# Board_v2.net
KiCad netlist of a schematic drawn in EAGLE
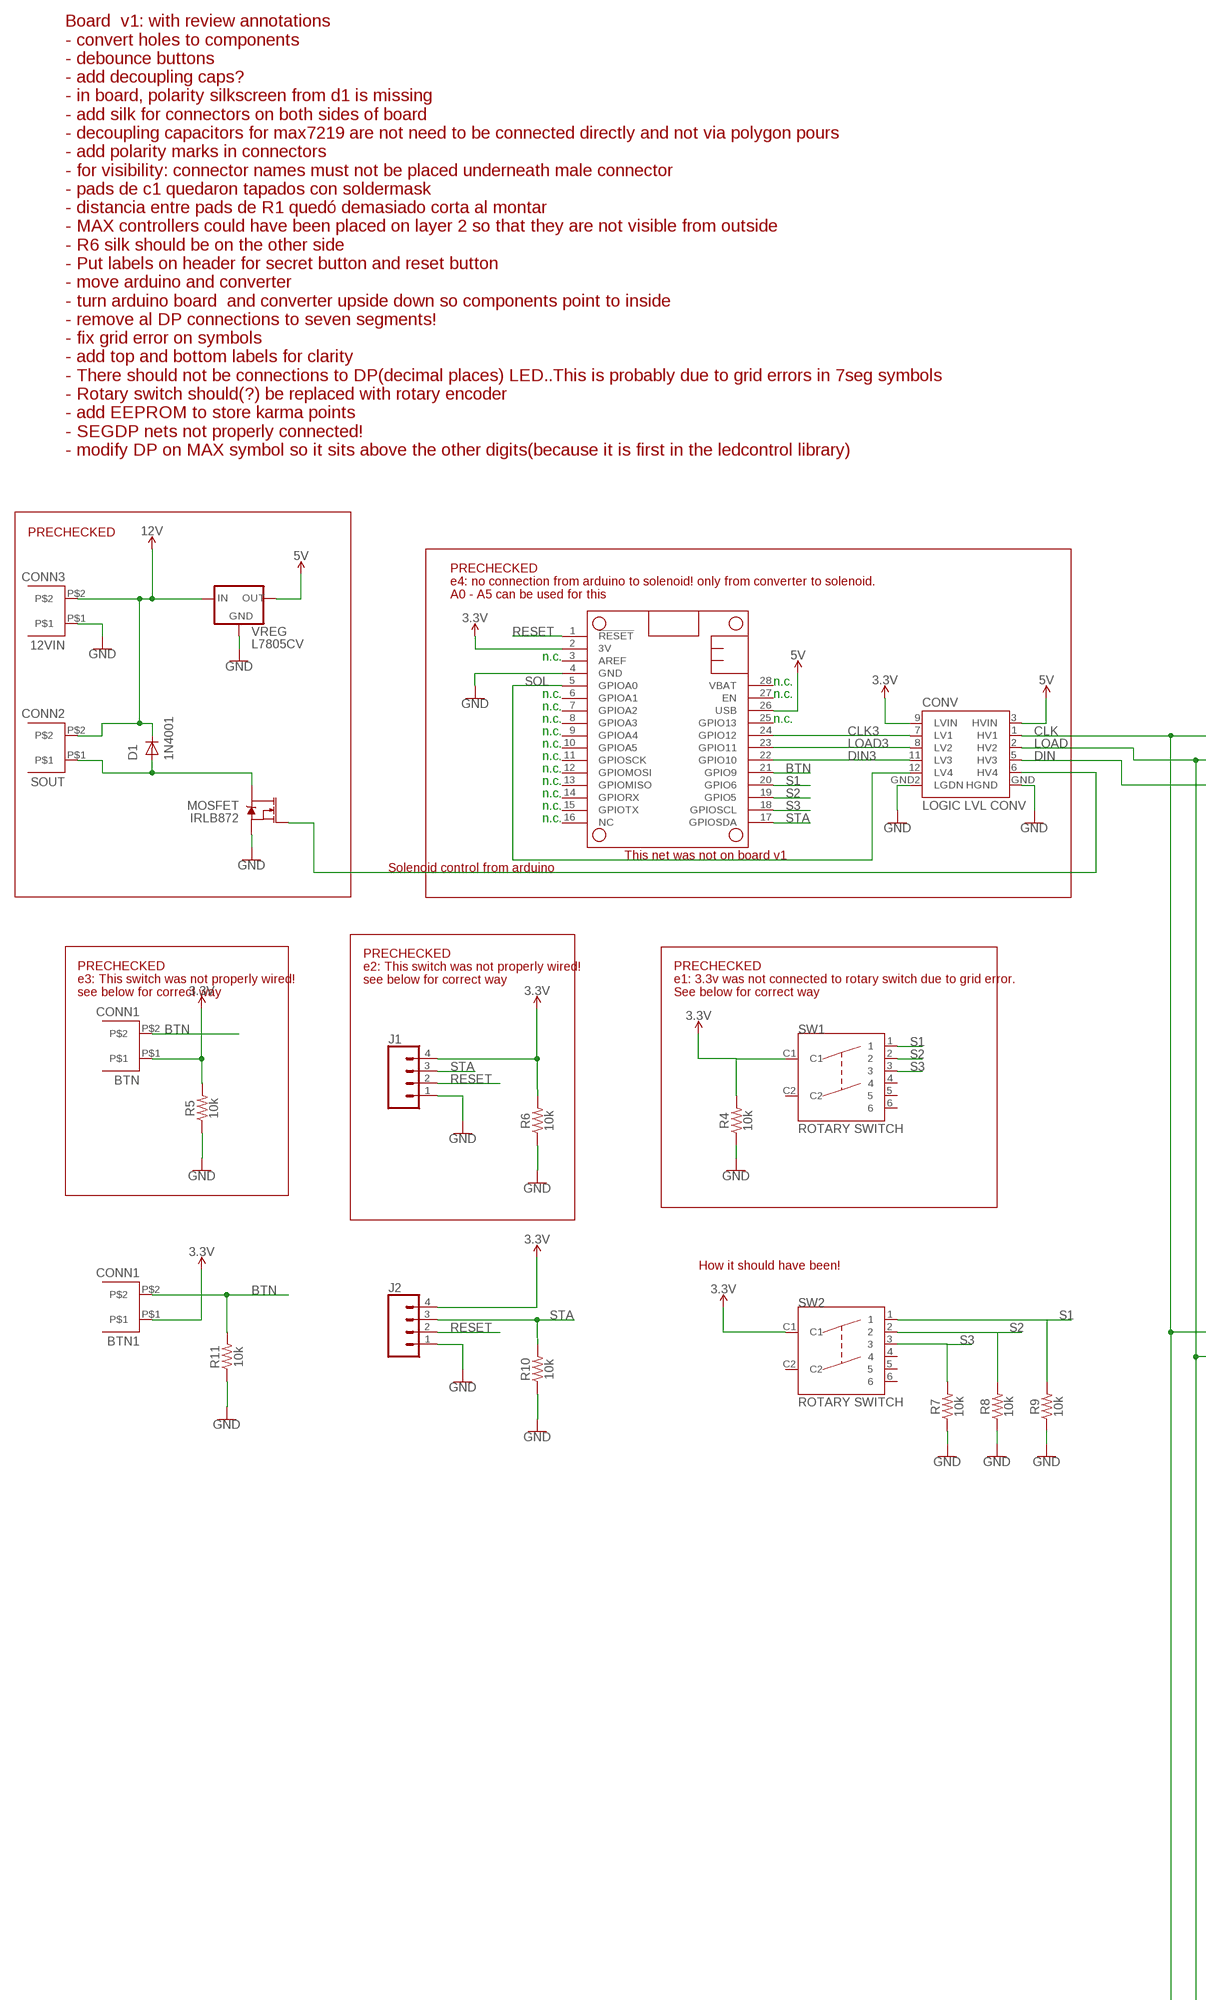
[diagram p0: schematic, sheet 1, part 1 of 3]
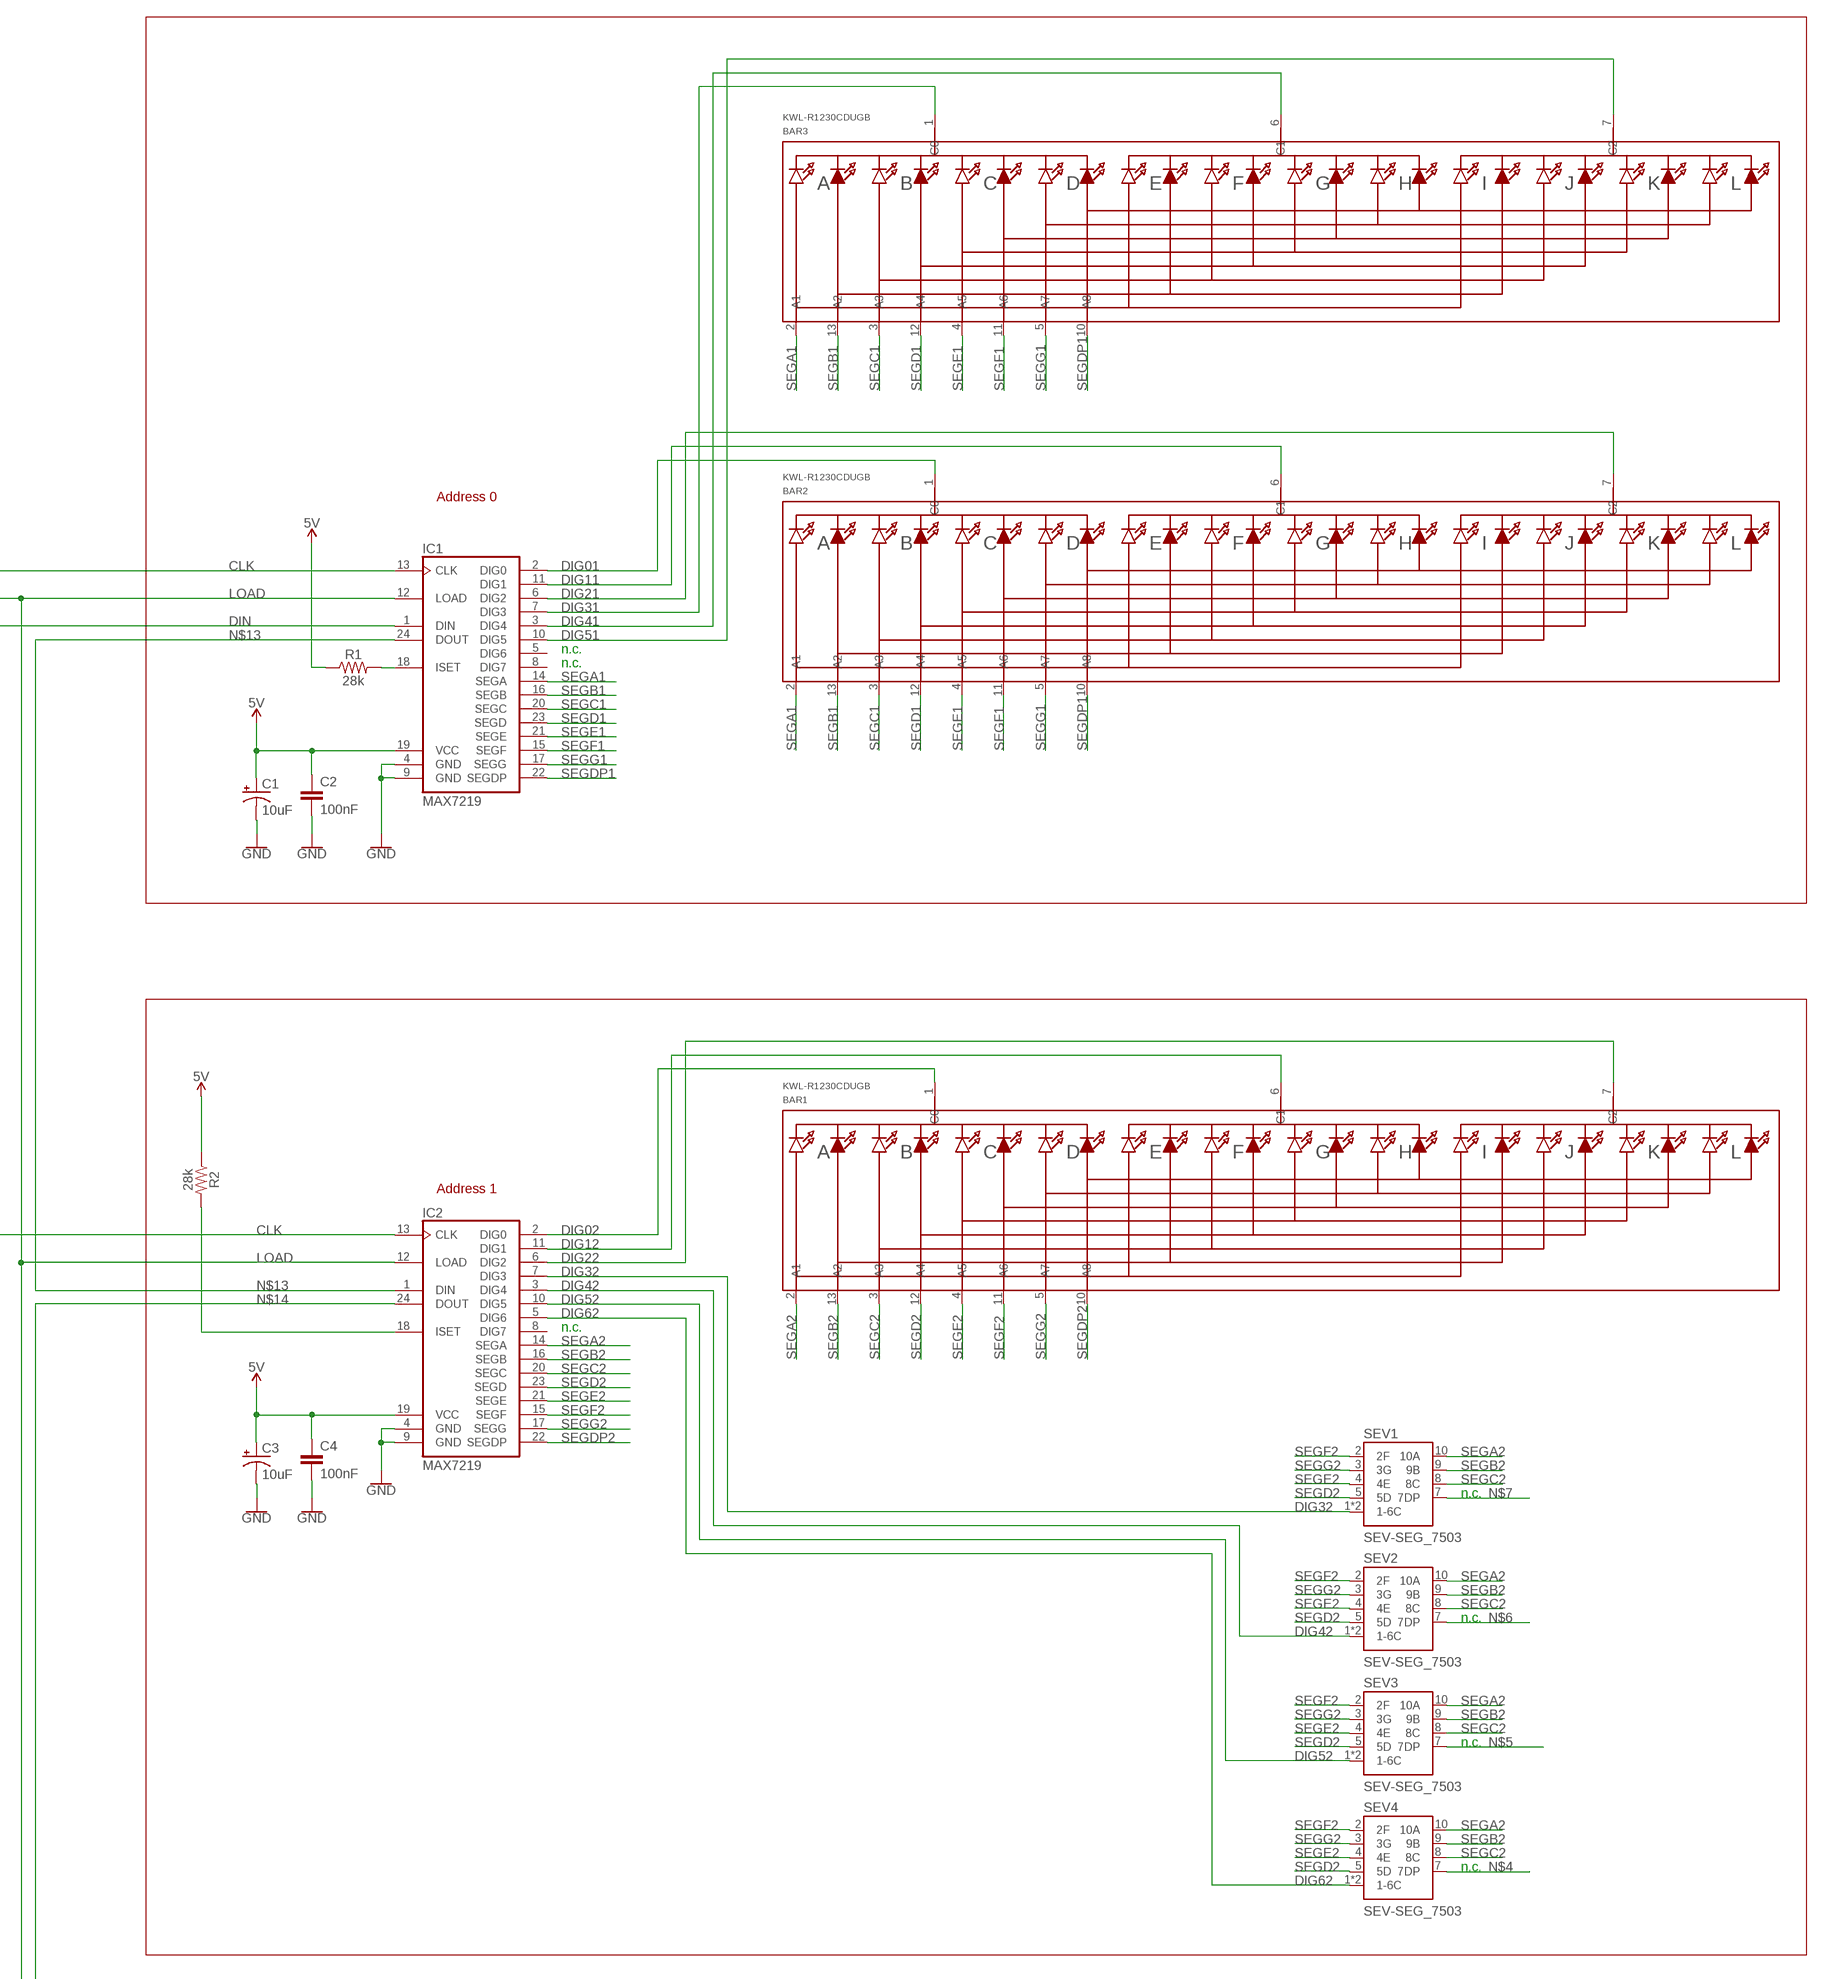
[diagram p1: schematic, sheet 1, part 2 of 3]
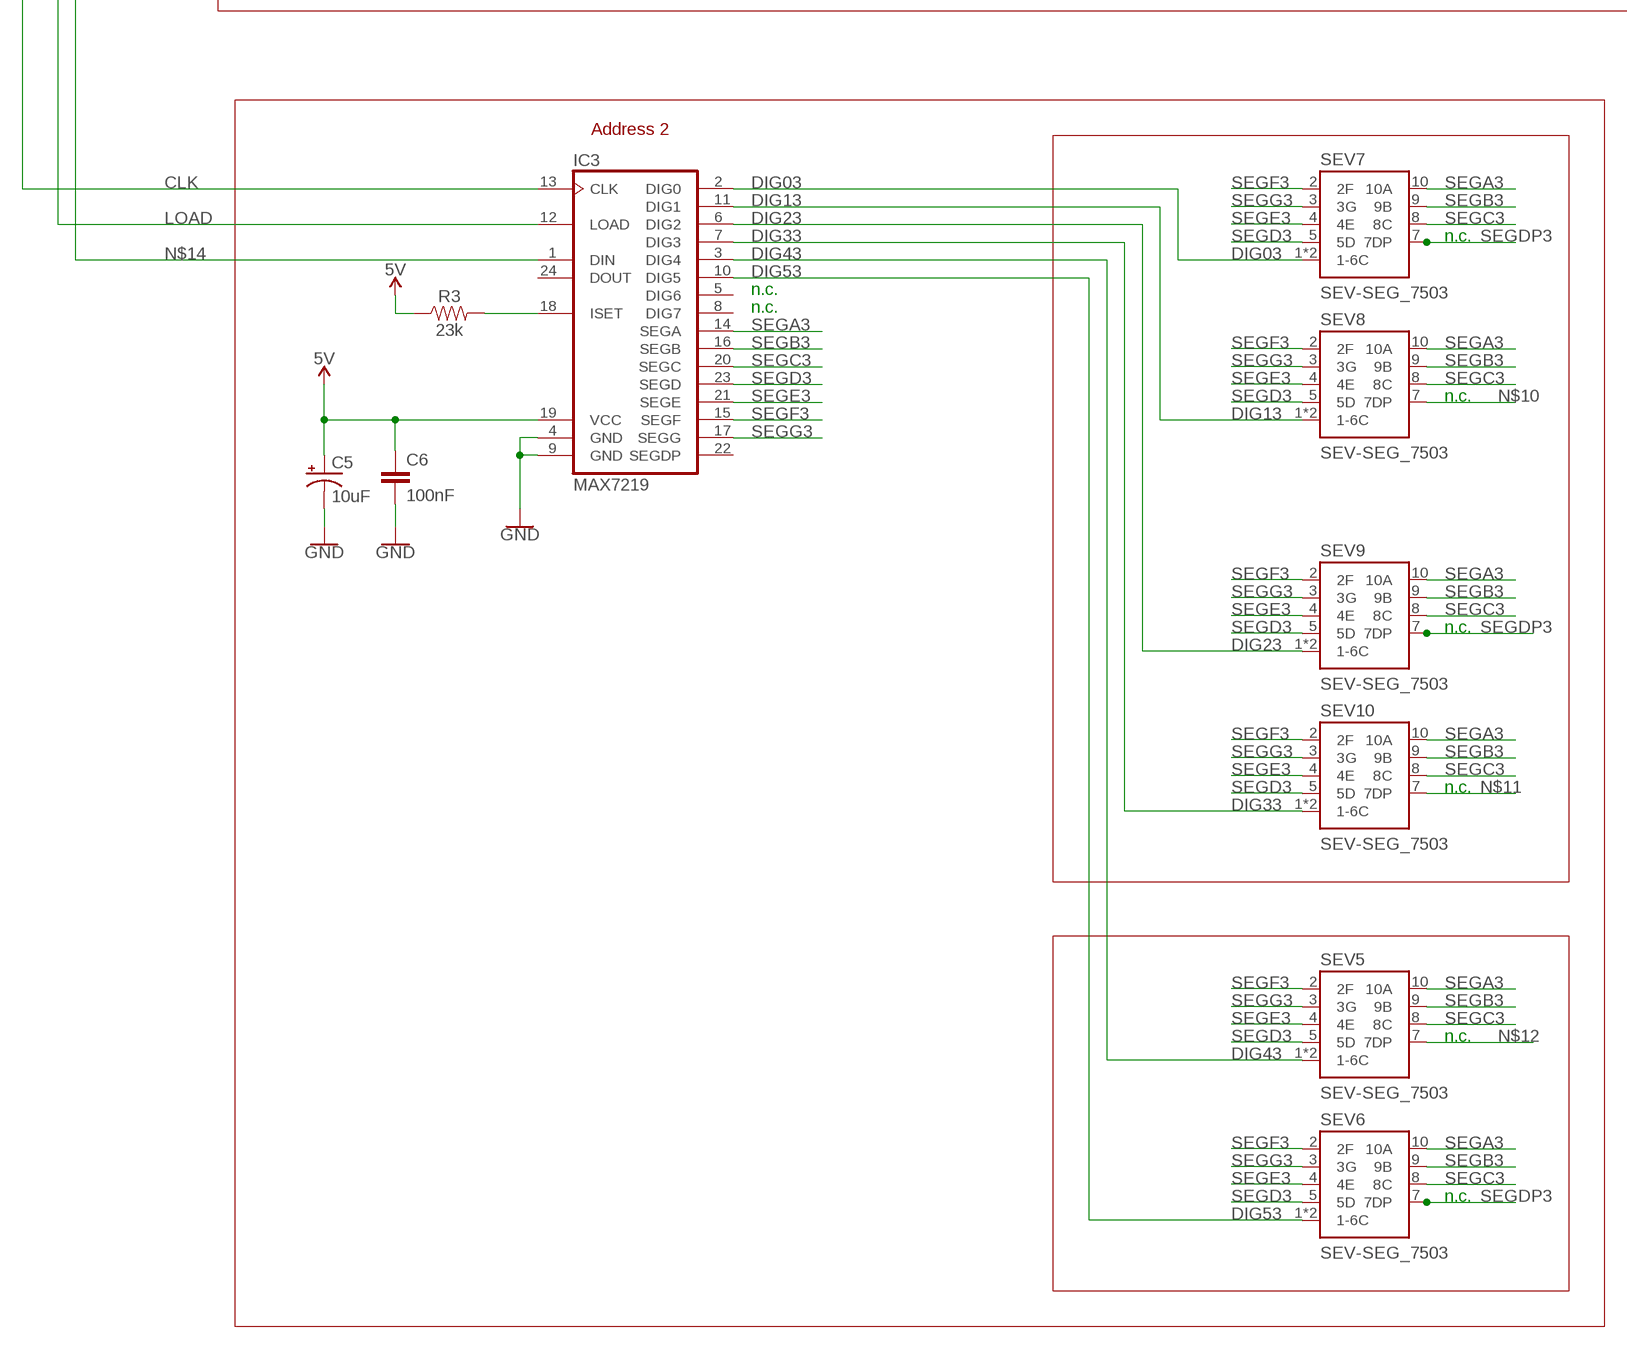
[diagram p2: schematic, sheet 1, part 3 of 3]

(export (version "E")
  (design (tool "Eeschema 10.0.6"))
  (components
    (comp (ref "12VIN")
      (value "CONN3")
      (footprint "eagle-import:MICRO-FIT_43560_3MM")
      (libsource (lib "eagle-import") (part "MICRO-FIT_3.0_43650"))
    )
    (comp (ref "BAR1")
      (value "KWL-R1230CDUGB")
      (footprint "eagle-import:SEGMENT_BICOL_BL-AR12Z3010")
      (libsource (lib "eagle-import") (part "KWL-R1230CDUGB"))
    )
    (comp (ref "BAR2")
      (value "KWL-R1230CDUGB")
      (footprint "eagle-import:SEGMENT_BICOL_BL-AR12Z3010")
      (libsource (lib "eagle-import") (part "KWL-R1230CDUGB"))
    )
    (comp (ref "BAR3")
      (value "KWL-R1230CDUGB")
      (footprint "eagle-import:SEGMENT_BICOL_BL-AR12Z3010")
      (libsource (lib "eagle-import") (part "KWL-R1230CDUGB"))
    )
    (comp (ref "BTN")
      (value "CONN1")
      (footprint "eagle-import:MICRO-FIT_43560_3MM")
      (libsource (lib "eagle-import") (part "MICRO-FIT_3.0_43650"))
    )
    (comp (ref "BTN1")
      (value "CONN1")
      (footprint "eagle-import:MICRO-FIT_43560_3MM")
      (libsource (lib "eagle-import") (part "MICRO-FIT_3.0_43650"))
    )
    (comp (ref "C1")
      (value "10uF")
      (footprint "eagle-import:CPOL-RADIAL-2.5MM-5MM-KIT")
      (libsource (lib "eagle-import") (part "CAP_POL"))
    )
    (comp (ref "C2")
      (value "100nF")
      (footprint "eagle-import:CAP-PTH-5MM")
      (libsource (lib "eagle-import") (part "CAP_CERAMIC"))
    )
    (comp (ref "C3")
      (value "10uF")
      (footprint "eagle-import:CPOL-RADIAL-2.5MM-5MM-KIT")
      (libsource (lib "eagle-import") (part "CAP_POL"))
    )
    (comp (ref "C4")
      (value "100nF")
      (footprint "eagle-import:CAP-PTH-5MM")
      (libsource (lib "eagle-import") (part "CAP_CERAMIC"))
    )
    (comp (ref "C5")
      (value "10uF")
      (footprint "eagle-import:CPOL-RADIAL-2.5MM-5MM-KIT")
      (libsource (lib "eagle-import") (part "CAP_POL"))
    )
    (comp (ref "C6")
      (value "100nF")
      (footprint "eagle-import:CAP-PTH-5MM")
      (libsource (lib "eagle-import") (part "CAP_CERAMIC"))
    )
    (comp (ref "CONV")
      (value "LOGIC LVL CONV")
      (footprint "eagle-import:3-5V_LOGIC_LVL_CONV")
      (libsource (lib "eagle-import") (part "3-5V_LOGIC_LVL_CONV"))
    )
    (comp (ref "D1")
      (value "1N4001")
      (footprint "eagle-import:CASE59−10-AXIAL")
      (libsource (lib "eagle-import") (part "1N4001"))
    )
    (comp (ref "FEATHERM0")
      (value "FEATHERWING_NODIM")
      (footprint "eagle-import:FEATHER")
      (libsource (lib "eagle-import") (part "FEATHERWING_NODIM"))
    )
    (comp (ref "IC1")
      (value "MAX7219")
      (footprint "eagle-import:DIL24-3")
      (fields (field (name "MF") "MAXIM") (field (name "MPN") "MAX7219CNG"))
      (libsource (lib "eagle-import") (part "MAX7219CNG"))
    )
    (comp (ref "IC2")
      (value "MAX7219")
      (footprint "eagle-import:DIL24-3")
      (fields (field (name "MF") "MAXIM") (field (name "MPN") "MAX7219CNG"))
      (libsource (lib "eagle-import") (part "MAX7219CNG"))
    )
    (comp (ref "IC3")
      (value "MAX7219")
      (footprint "eagle-import:DIL24-3")
      (fields (field (name "MF") "MAXIM") (field (name "MPN") "MAX7219CNG"))
      (libsource (lib "eagle-import") (part "MAX7219CNG"))
    )
    (comp (ref "J1")
      (value "CONN_041X04_NO_SILK")
      (footprint "eagle-import:1X04_NO_SILK")
      (libsource (lib "eagle-import") (part "CONN_041X04_NO_SILK"))
    )
    (comp (ref "J2")
      (value "CONN_041X04_NO_SILK")
      (footprint "eagle-import:1X04_NO_SILK")
      (libsource (lib "eagle-import") (part "CONN_041X04_NO_SILK"))
    )
    (comp (ref "MOSFET")
      (value "IRLB872")
      (footprint "eagle-import:TO-220-ALT")
      (libsource (lib "eagle-import") (part "IRLB872"))
    )
    (comp (ref "R1")
      (value "28k")
      (footprint "eagle-import:AXIAL-0.3")
      (libsource (lib "eagle-import") (part "RESISTOR"))
    )
    (comp (ref "R2")
      (value "28k")
      (footprint "eagle-import:AXIAL-0.3")
      (libsource (lib "eagle-import") (part "RESISTOR"))
    )
    (comp (ref "R3")
      (value "23k")
      (footprint "eagle-import:AXIAL-0.3")
      (libsource (lib "eagle-import") (part "RESISTOR"))
    )
    (comp (ref "R4")
      (value "10k")
      (footprint "eagle-import:AXIAL-0.3")
      (libsource (lib "eagle-import") (part "RESISTOR"))
    )
    (comp (ref "R5")
      (value "10k")
      (footprint "eagle-import:AXIAL-0.3")
      (libsource (lib "eagle-import") (part "RESISTOR"))
    )
    (comp (ref "R6")
      (value "10k")
      (footprint "eagle-import:AXIAL-0.3")
      (libsource (lib "eagle-import") (part "RESISTOR"))
    )
    (comp (ref "R7")
      (value "10k")
      (footprint "eagle-import:AXIAL-0.3")
      (libsource (lib "eagle-import") (part "RESISTOR"))
    )
    (comp (ref "R8")
      (value "10k")
      (footprint "eagle-import:AXIAL-0.3")
      (libsource (lib "eagle-import") (part "RESISTOR"))
    )
    (comp (ref "R9")
      (value "10k")
      (footprint "eagle-import:AXIAL-0.3")
      (libsource (lib "eagle-import") (part "RESISTOR"))
    )
    (comp (ref "R10")
      (value "10k")
      (footprint "eagle-import:AXIAL-0.3")
      (libsource (lib "eagle-import") (part "RESISTOR"))
    )
    (comp (ref "R11")
      (value "10k")
      (footprint "eagle-import:AXIAL-0.3")
      (libsource (lib "eagle-import") (part "RESISTOR"))
    )
    (comp (ref "SEV1")
      (value "SEV-SEG_7503")
      (footprint "eagle-import:HDSP-7503-C")
      (libsource (lib "eagle-import") (part "SEV-SEG_7503"))
    )
    (comp (ref "SEV2")
      (value "SEV-SEG_7503")
      (footprint "eagle-import:HDSP-7503-C")
      (libsource (lib "eagle-import") (part "SEV-SEG_7503"))
    )
    (comp (ref "SEV3")
      (value "SEV-SEG_7503")
      (footprint "eagle-import:HDSP-7503-C")
      (libsource (lib "eagle-import") (part "SEV-SEG_7503"))
    )
    (comp (ref "SEV4")
      (value "SEV-SEG_7503")
      (footprint "eagle-import:HDSP-7503-C")
      (libsource (lib "eagle-import") (part "SEV-SEG_7503"))
    )
    (comp (ref "SEV5")
      (value "SEV-SEG_7503")
      (footprint "eagle-import:HDSP-7503-C")
      (libsource (lib "eagle-import") (part "SEV-SEG_7503"))
    )
    (comp (ref "SEV6")
      (value "SEV-SEG_7503")
      (footprint "eagle-import:HDSP-7503-C")
      (libsource (lib "eagle-import") (part "SEV-SEG_7503"))
    )
    (comp (ref "SEV7")
      (value "SEV-SEG_7503")
      (footprint "eagle-import:HDSP-7503-C")
      (libsource (lib "eagle-import") (part "SEV-SEG_7503"))
    )
    (comp (ref "SEV8")
      (value "SEV-SEG_7503")
      (footprint "eagle-import:HDSP-7503-C")
      (libsource (lib "eagle-import") (part "SEV-SEG_7503"))
    )
    (comp (ref "SEV9")
      (value "SEV-SEG_7503")
      (footprint "eagle-import:HDSP-7503-C")
      (libsource (lib "eagle-import") (part "SEV-SEG_7503"))
    )
    (comp (ref "SEV10")
      (value "SEV-SEG_7503")
      (footprint "eagle-import:HDSP-7503-C")
      (libsource (lib "eagle-import") (part "SEV-SEG_7503"))
    )
    (comp (ref "SOUT")
      (value "CONN2")
      (footprint "eagle-import:MICRO-FIT_43560_3MM")
      (libsource (lib "eagle-import") (part "MICRO-FIT_3.0_43650"))
    )
    (comp (ref "SW1")
      (value "ROTARY SWITCH")
      (footprint "eagle-import:MRB24B_SP3T")
      (libsource (lib "eagle-import") (part "MRB_ROTARY_SWITCH"))
    )
    (comp (ref "SW2")
      (value "ROTARY SWITCH")
      (footprint "eagle-import:MRB24B_SP3T")
      (libsource (lib "eagle-import") (part "MRB_ROTARY_SWITCH"))
    )
    (comp (ref "VREG")
      (value "L7805CV")
      (footprint "eagle-import:TO-220-ALT")
      (libsource (lib "eagle-import") (part "L7805CV"))
    )
  )
  (nets
    (net (code "1") (name "/BTN") (class "Default")
      (node (ref "BTN") (pin "P$2") (pinfunction "P$2_P$2") (pintype "bidirectional"))
      (node (ref "BTN1") (pin "P$2") (pinfunction "P$2_P$2") (pintype "bidirectional"))
      (node (ref "FEATHERM0") (pin "21") (pinfunction "GPIO9_21") (pintype "bidirectional"))
      (node (ref "R11") (pin "P$2") (pinfunction "2_P$2") (pintype "passive"))
    )
    (net (code "2") (name "/CLK") (class "Default")
      (node (ref "CONV") (pin "1") (pinfunction "HV1_1") (pintype "bidirectional"))
      (node (ref "IC1") (pin "13") (pinfunction "CLK_13") (pintype "input"))
      (node (ref "IC2") (pin "13") (pinfunction "CLK_13") (pintype "input"))
      (node (ref "IC3") (pin "13") (pinfunction "CLK_13") (pintype "input"))
    )
    (net (code "3") (name "/CLK3") (class "Default")
      (node (ref "CONV") (pin "7") (pinfunction "LV1_7") (pintype "bidirectional"))
      (node (ref "FEATHERM0") (pin "24") (pinfunction "GPIO12_24") (pintype "bidirectional"))
    )
    (net (code "4") (name "/DIG01") (class "Default")
      (node (ref "BAR2") (pin "1") (pinfunction "C0_1") (pintype "bidirectional"))
      (node (ref "IC1") (pin "2") (pinfunction "DIG0_2") (pintype "output"))
    )
    (net (code "5") (name "/DIG02") (class "Default")
      (node (ref "BAR1") (pin "1") (pinfunction "C0_1") (pintype "bidirectional"))
      (node (ref "IC2") (pin "2") (pinfunction "DIG0_2") (pintype "output"))
    )
    (net (code "6") (name "/DIG03") (class "Default")
      (node (ref "IC3") (pin "2") (pinfunction "DIG0_2") (pintype "output"))
      (node (ref "SEV7") (pin "1") (pinfunction "1-6C_1") (pintype "bidirectional"))
      (node (ref "SEV7") (pin "6") (pinfunction "1-6C_6") (pintype "bidirectional"))
    )
    (net (code "7") (name "/DIG11") (class "Default")
      (node (ref "BAR2") (pin "6") (pinfunction "C1_6") (pintype "bidirectional"))
      (node (ref "IC1") (pin "11") (pinfunction "DIG1_11") (pintype "output"))
    )
    (net (code "8") (name "/DIG12") (class "Default")
      (node (ref "BAR1") (pin "6") (pinfunction "C1_6") (pintype "bidirectional"))
      (node (ref "IC2") (pin "11") (pinfunction "DIG1_11") (pintype "output"))
    )
    (net (code "9") (name "/DIG13") (class "Default")
      (node (ref "IC3") (pin "11") (pinfunction "DIG1_11") (pintype "output"))
      (node (ref "SEV8") (pin "1") (pinfunction "1-6C_1") (pintype "bidirectional"))
      (node (ref "SEV8") (pin "6") (pinfunction "1-6C_6") (pintype "bidirectional"))
    )
    (net (code "10") (name "/DIG21") (class "Default")
      (node (ref "BAR2") (pin "7") (pinfunction "C2_7") (pintype "bidirectional"))
      (node (ref "IC1") (pin "6") (pinfunction "DIG2_6") (pintype "output"))
    )
    (net (code "11") (name "/DIG22") (class "Default")
      (node (ref "BAR1") (pin "7") (pinfunction "C2_7") (pintype "bidirectional"))
      (node (ref "IC2") (pin "6") (pinfunction "DIG2_6") (pintype "output"))
    )
    (net (code "12") (name "/DIG23") (class "Default")
      (node (ref "IC3") (pin "6") (pinfunction "DIG2_6") (pintype "output"))
      (node (ref "SEV9") (pin "1") (pinfunction "1-6C_1") (pintype "bidirectional"))
      (node (ref "SEV9") (pin "6") (pinfunction "1-6C_6") (pintype "bidirectional"))
    )
    (net (code "13") (name "/DIG31") (class "Default")
      (node (ref "BAR3") (pin "1") (pinfunction "C0_1") (pintype "bidirectional"))
      (node (ref "IC1") (pin "7") (pinfunction "DIG3_7") (pintype "output"))
    )
    (net (code "14") (name "/DIG32") (class "Default")
      (node (ref "IC2") (pin "7") (pinfunction "DIG3_7") (pintype "output"))
      (node (ref "SEV1") (pin "1") (pinfunction "1-6C_1") (pintype "bidirectional"))
      (node (ref "SEV1") (pin "6") (pinfunction "1-6C_6") (pintype "bidirectional"))
    )
    (net (code "15") (name "/DIG33") (class "Default")
      (node (ref "IC3") (pin "7") (pinfunction "DIG3_7") (pintype "output"))
      (node (ref "SEV10") (pin "1") (pinfunction "1-6C_1") (pintype "bidirectional"))
      (node (ref "SEV10") (pin "6") (pinfunction "1-6C_6") (pintype "bidirectional"))
    )
    (net (code "16") (name "/DIG41") (class "Default")
      (node (ref "BAR3") (pin "6") (pinfunction "C1_6") (pintype "bidirectional"))
      (node (ref "IC1") (pin "3") (pinfunction "DIG4_3") (pintype "output"))
    )
    (net (code "17") (name "/DIG42") (class "Default")
      (node (ref "IC2") (pin "3") (pinfunction "DIG4_3") (pintype "output"))
      (node (ref "SEV2") (pin "1") (pinfunction "1-6C_1") (pintype "bidirectional"))
      (node (ref "SEV2") (pin "6") (pinfunction "1-6C_6") (pintype "bidirectional"))
    )
    (net (code "18") (name "/DIG43") (class "Default")
      (node (ref "IC3") (pin "3") (pinfunction "DIG4_3") (pintype "output"))
      (node (ref "SEV5") (pin "1") (pinfunction "1-6C_1") (pintype "bidirectional"))
      (node (ref "SEV5") (pin "6") (pinfunction "1-6C_6") (pintype "bidirectional"))
    )
    (net (code "19") (name "/DIG51") (class "Default")
      (node (ref "BAR3") (pin "7") (pinfunction "C2_7") (pintype "bidirectional"))
      (node (ref "IC1") (pin "10") (pinfunction "DIG5_10") (pintype "output"))
    )
    (net (code "20") (name "/DIG52") (class "Default")
      (node (ref "IC2") (pin "10") (pinfunction "DIG5_10") (pintype "output"))
      (node (ref "SEV3") (pin "1") (pinfunction "1-6C_1") (pintype "bidirectional"))
      (node (ref "SEV3") (pin "6") (pinfunction "1-6C_6") (pintype "bidirectional"))
    )
    (net (code "21") (name "/DIG53") (class "Default")
      (node (ref "IC3") (pin "10") (pinfunction "DIG5_10") (pintype "output"))
      (node (ref "SEV6") (pin "1") (pinfunction "1-6C_1") (pintype "bidirectional"))
      (node (ref "SEV6") (pin "6") (pinfunction "1-6C_6") (pintype "bidirectional"))
    )
    (net (code "22") (name "/DIG62") (class "Default")
      (node (ref "IC2") (pin "5") (pinfunction "DIG6_5") (pintype "output"))
      (node (ref "SEV4") (pin "1") (pinfunction "1-6C_1") (pintype "bidirectional"))
      (node (ref "SEV4") (pin "6") (pinfunction "1-6C_6") (pintype "bidirectional"))
    )
    (net (code "23") (name "/DIN") (class "Default")
      (node (ref "CONV") (pin "5") (pinfunction "HV3_5") (pintype "bidirectional"))
      (node (ref "IC1") (pin "1") (pinfunction "DIN_1") (pintype "input"))
    )
    (net (code "24") (name "/DIN3") (class "Default")
      (node (ref "CONV") (pin "11") (pinfunction "LV3_11") (pintype "bidirectional"))
      (node (ref "FEATHERM0") (pin "22") (pinfunction "GPIO10_22") (pintype "bidirectional"))
    )
    (net (code "25") (name "/LOAD") (class "Default")
      (node (ref "CONV") (pin "2") (pinfunction "HV2_2") (pintype "bidirectional"))
      (node (ref "IC1") (pin "12") (pinfunction "LOAD_12") (pintype "input"))
      (node (ref "IC2") (pin "12") (pinfunction "LOAD_12") (pintype "input"))
      (node (ref "IC3") (pin "12") (pinfunction "LOAD_12") (pintype "input"))
    )
    (net (code "26") (name "/LOAD3") (class "Default")
      (node (ref "CONV") (pin "8") (pinfunction "LV2_8") (pintype "bidirectional"))
      (node (ref "FEATHERM0") (pin "23") (pinfunction "GPIO11_23") (pintype "bidirectional"))
    )
    (net (code "27") (name "/N$4") (class "Default")
      (node (ref "SEV4") (pin "7") (pinfunction "7DP_7") (pintype "bidirectional"))
    )
    (net (code "28") (name "/N$5") (class "Default")
      (node (ref "SEV3") (pin "7") (pinfunction "7DP_7") (pintype "bidirectional"))
    )
    (net (code "29") (name "/N$6") (class "Default")
      (node (ref "SEV2") (pin "7") (pinfunction "7DP_7") (pintype "bidirectional"))
    )
    (net (code "30") (name "/N$7") (class "Default")
      (node (ref "SEV1") (pin "7") (pinfunction "7DP_7") (pintype "bidirectional"))
    )
    (net (code "31") (name "/N$10") (class "Default")
      (node (ref "SEV8") (pin "7") (pinfunction "7DP_7") (pintype "bidirectional"))
    )
    (net (code "32") (name "/N$11") (class "Default")
      (node (ref "SEV10") (pin "7") (pinfunction "7DP_7") (pintype "bidirectional"))
    )
    (net (code "33") (name "/N$12") (class "Default")
      (node (ref "SEV5") (pin "7") (pinfunction "7DP_7") (pintype "bidirectional"))
    )
    (net (code "34") (name "/N$13") (class "Default")
      (node (ref "IC1") (pin "24") (pinfunction "DOUT_24") (pintype "output"))
      (node (ref "IC2") (pin "1") (pinfunction "DIN_1") (pintype "input"))
    )
    (net (code "35") (name "/N$14") (class "Default")
      (node (ref "IC2") (pin "24") (pinfunction "DOUT_24") (pintype "output"))
      (node (ref "IC3") (pin "1") (pinfunction "DIN_1") (pintype "input"))
    )
    (net (code "36") (name "/RESET") (class "Default")
      (node (ref "FEATHERM0") (pin "1") (pinfunction "~{RESET}_1") (pintype "input"))
      (node (ref "J1") (pin "2") (pinfunction "2_2") (pintype "passive"))
      (node (ref "J2") (pin "2") (pinfunction "2_2") (pintype "passive"))
    )
    (net (code "37") (name "/S1") (class "Default")
      (node (ref "FEATHERM0") (pin "20") (pinfunction "GPIO6_20") (pintype "bidirectional"))
      (node (ref "R9") (pin "P$2") (pinfunction "2_P$2") (pintype "passive"))
      (node (ref "SW1") (pin "1") (pinfunction "1_1") (pintype "bidirectional"))
      (node (ref "SW2") (pin "1") (pinfunction "1_1") (pintype "bidirectional"))
    )
    (net (code "38") (name "/S2") (class "Default")
      (node (ref "FEATHERM0") (pin "19") (pinfunction "GPIO5_19") (pintype "bidirectional"))
      (node (ref "R8") (pin "P$2") (pinfunction "2_P$2") (pintype "passive"))
      (node (ref "SW1") (pin "2") (pinfunction "2_2") (pintype "bidirectional"))
      (node (ref "SW2") (pin "2") (pinfunction "2_2") (pintype "bidirectional"))
    )
    (net (code "39") (name "/S3") (class "Default")
      (node (ref "FEATHERM0") (pin "18") (pinfunction "GPIOSCL_18") (pintype "bidirectional"))
      (node (ref "R7") (pin "P$2") (pinfunction "2_P$2") (pintype "passive"))
      (node (ref "SW1") (pin "3") (pinfunction "3_3") (pintype "bidirectional"))
      (node (ref "SW2") (pin "3") (pinfunction "3_3") (pintype "bidirectional"))
    )
    (net (code "40") (name "/SEGA1") (class "Default")
      (node (ref "BAR2") (pin "2") (pinfunction "A1_2") (pintype "bidirectional"))
      (node (ref "BAR3") (pin "2") (pinfunction "A1_2") (pintype "bidirectional"))
      (node (ref "IC1") (pin "14") (pinfunction "SEGA_14") (pintype "output"))
    )
    (net (code "41") (name "/SEGA2") (class "Default")
      (node (ref "BAR1") (pin "2") (pinfunction "A1_2") (pintype "bidirectional"))
      (node (ref "IC2") (pin "14") (pinfunction "SEGA_14") (pintype "output"))
      (node (ref "SEV1") (pin "10") (pinfunction "10A_10") (pintype "bidirectional"))
      (node (ref "SEV2") (pin "10") (pinfunction "10A_10") (pintype "bidirectional"))
      (node (ref "SEV3") (pin "10") (pinfunction "10A_10") (pintype "bidirectional"))
      (node (ref "SEV4") (pin "10") (pinfunction "10A_10") (pintype "bidirectional"))
    )
    (net (code "42") (name "/SEGA3") (class "Default")
      (node (ref "IC3") (pin "14") (pinfunction "SEGA_14") (pintype "output"))
      (node (ref "SEV10") (pin "10") (pinfunction "10A_10") (pintype "bidirectional"))
      (node (ref "SEV5") (pin "10") (pinfunction "10A_10") (pintype "bidirectional"))
      (node (ref "SEV6") (pin "10") (pinfunction "10A_10") (pintype "bidirectional"))
      (node (ref "SEV7") (pin "10") (pinfunction "10A_10") (pintype "bidirectional"))
      (node (ref "SEV8") (pin "10") (pinfunction "10A_10") (pintype "bidirectional"))
      (node (ref "SEV9") (pin "10") (pinfunction "10A_10") (pintype "bidirectional"))
    )
    (net (code "43") (name "/SEGB1") (class "Default")
      (node (ref "BAR2") (pin "13") (pinfunction "A2_13") (pintype "bidirectional"))
      (node (ref "BAR3") (pin "13") (pinfunction "A2_13") (pintype "bidirectional"))
      (node (ref "IC1") (pin "16") (pinfunction "SEGB_16") (pintype "output"))
    )
    (net (code "44") (name "/SEGB2") (class "Default")
      (node (ref "BAR1") (pin "13") (pinfunction "A2_13") (pintype "bidirectional"))
      (node (ref "IC2") (pin "16") (pinfunction "SEGB_16") (pintype "output"))
      (node (ref "SEV1") (pin "9") (pinfunction "9B_9") (pintype "bidirectional"))
      (node (ref "SEV2") (pin "9") (pinfunction "9B_9") (pintype "bidirectional"))
      (node (ref "SEV3") (pin "9") (pinfunction "9B_9") (pintype "bidirectional"))
      (node (ref "SEV4") (pin "9") (pinfunction "9B_9") (pintype "bidirectional"))
    )
    (net (code "45") (name "/SEGB3") (class "Default")
      (node (ref "IC3") (pin "16") (pinfunction "SEGB_16") (pintype "output"))
      (node (ref "SEV10") (pin "9") (pinfunction "9B_9") (pintype "bidirectional"))
      (node (ref "SEV5") (pin "9") (pinfunction "9B_9") (pintype "bidirectional"))
      (node (ref "SEV6") (pin "9") (pinfunction "9B_9") (pintype "bidirectional"))
      (node (ref "SEV7") (pin "9") (pinfunction "9B_9") (pintype "bidirectional"))
      (node (ref "SEV8") (pin "9") (pinfunction "9B_9") (pintype "bidirectional"))
      (node (ref "SEV9") (pin "9") (pinfunction "9B_9") (pintype "bidirectional"))
    )
    (net (code "46") (name "/SEGC1") (class "Default")
      (node (ref "BAR2") (pin "3") (pinfunction "A3_3") (pintype "bidirectional"))
      (node (ref "BAR3") (pin "3") (pinfunction "A3_3") (pintype "bidirectional"))
      (node (ref "IC1") (pin "20") (pinfunction "SEGC_20") (pintype "output"))
    )
    (net (code "47") (name "/SEGC2") (class "Default")
      (node (ref "BAR1") (pin "3") (pinfunction "A3_3") (pintype "bidirectional"))
      (node (ref "IC2") (pin "20") (pinfunction "SEGC_20") (pintype "output"))
      (node (ref "SEV1") (pin "8") (pinfunction "8C_8") (pintype "bidirectional"))
      (node (ref "SEV2") (pin "8") (pinfunction "8C_8") (pintype "bidirectional"))
      (node (ref "SEV3") (pin "8") (pinfunction "8C_8") (pintype "bidirectional"))
      (node (ref "SEV4") (pin "8") (pinfunction "8C_8") (pintype "bidirectional"))
    )
    (net (code "48") (name "/SEGC3") (class "Default")
      (node (ref "IC3") (pin "20") (pinfunction "SEGC_20") (pintype "output"))
      (node (ref "SEV10") (pin "8") (pinfunction "8C_8") (pintype "bidirectional"))
      (node (ref "SEV5") (pin "8") (pinfunction "8C_8") (pintype "bidirectional"))
      (node (ref "SEV6") (pin "8") (pinfunction "8C_8") (pintype "bidirectional"))
      (node (ref "SEV7") (pin "8") (pinfunction "8C_8") (pintype "bidirectional"))
      (node (ref "SEV8") (pin "8") (pinfunction "8C_8") (pintype "bidirectional"))
      (node (ref "SEV9") (pin "8") (pinfunction "8C_8") (pintype "bidirectional"))
    )
    (net (code "49") (name "/SEGD1") (class "Default")
      (node (ref "BAR2") (pin "12") (pinfunction "A4_12") (pintype "bidirectional"))
      (node (ref "BAR3") (pin "12") (pinfunction "A4_12") (pintype "bidirectional"))
      (node (ref "IC1") (pin "23") (pinfunction "SEGD_23") (pintype "output"))
    )
    (net (code "50") (name "/SEGD2") (class "Default")
      (node (ref "BAR1") (pin "12") (pinfunction "A4_12") (pintype "bidirectional"))
      (node (ref "IC2") (pin "23") (pinfunction "SEGD_23") (pintype "output"))
      (node (ref "SEV1") (pin "5") (pinfunction "5D_5") (pintype "bidirectional"))
      (node (ref "SEV2") (pin "5") (pinfunction "5D_5") (pintype "bidirectional"))
      (node (ref "SEV3") (pin "5") (pinfunction "5D_5") (pintype "bidirectional"))
      (node (ref "SEV4") (pin "5") (pinfunction "5D_5") (pintype "bidirectional"))
    )
    (net (code "51") (name "/SEGD3") (class "Default")
      (node (ref "IC3") (pin "23") (pinfunction "SEGD_23") (pintype "output"))
      (node (ref "SEV10") (pin "5") (pinfunction "5D_5") (pintype "bidirectional"))
      (node (ref "SEV5") (pin "5") (pinfunction "5D_5") (pintype "bidirectional"))
      (node (ref "SEV6") (pin "5") (pinfunction "5D_5") (pintype "bidirectional"))
      (node (ref "SEV7") (pin "5") (pinfunction "5D_5") (pintype "bidirectional"))
      (node (ref "SEV8") (pin "5") (pinfunction "5D_5") (pintype "bidirectional"))
      (node (ref "SEV9") (pin "5") (pinfunction "5D_5") (pintype "bidirectional"))
    )
    (net (code "52") (name "/SEGDP1") (class "Default")
      (node (ref "BAR2") (pin "10") (pinfunction "A8_10") (pintype "bidirectional"))
      (node (ref "BAR3") (pin "10") (pinfunction "A8_10") (pintype "bidirectional"))
      (node (ref "IC1") (pin "22") (pinfunction "SEGDP_22") (pintype "output"))
    )
    (net (code "53") (name "/SEGDP2") (class "Default")
      (node (ref "BAR1") (pin "10") (pinfunction "A8_10") (pintype "bidirectional"))
      (node (ref "IC2") (pin "22") (pinfunction "SEGDP_22") (pintype "output"))
    )
    (net (code "54") (name "/SEGDP3") (class "Default")
      (node (ref "SEV6") (pin "7") (pinfunction "7DP_7") (pintype "bidirectional"))
      (node (ref "SEV7") (pin "7") (pinfunction "7DP_7") (pintype "bidirectional"))
      (node (ref "SEV9") (pin "7") (pinfunction "7DP_7") (pintype "bidirectional"))
    )
    (net (code "55") (name "/SEGE1") (class "Default")
      (node (ref "BAR2") (pin "4") (pinfunction "A5_4") (pintype "bidirectional"))
      (node (ref "BAR3") (pin "4") (pinfunction "A5_4") (pintype "bidirectional"))
      (node (ref "IC1") (pin "21") (pinfunction "SEGE_21") (pintype "output"))
    )
    (net (code "56") (name "/SEGE2") (class "Default")
      (node (ref "BAR1") (pin "4") (pinfunction "A5_4") (pintype "bidirectional"))
      (node (ref "IC2") (pin "21") (pinfunction "SEGE_21") (pintype "output"))
      (node (ref "SEV1") (pin "4") (pinfunction "4E_4") (pintype "bidirectional"))
      (node (ref "SEV2") (pin "4") (pinfunction "4E_4") (pintype "bidirectional"))
      (node (ref "SEV3") (pin "4") (pinfunction "4E_4") (pintype "bidirectional"))
      (node (ref "SEV4") (pin "4") (pinfunction "4E_4") (pintype "bidirectional"))
    )
    (net (code "57") (name "/SEGE3") (class "Default")
      (node (ref "IC3") (pin "21") (pinfunction "SEGE_21") (pintype "output"))
      (node (ref "SEV10") (pin "4") (pinfunction "4E_4") (pintype "bidirectional"))
      (node (ref "SEV5") (pin "4") (pinfunction "4E_4") (pintype "bidirectional"))
      (node (ref "SEV6") (pin "4") (pinfunction "4E_4") (pintype "bidirectional"))
      (node (ref "SEV7") (pin "4") (pinfunction "4E_4") (pintype "bidirectional"))
      (node (ref "SEV8") (pin "4") (pinfunction "4E_4") (pintype "bidirectional"))
      (node (ref "SEV9") (pin "4") (pinfunction "4E_4") (pintype "bidirectional"))
    )
    (net (code "58") (name "/SEGF1") (class "Default")
      (node (ref "BAR2") (pin "11") (pinfunction "A6_11") (pintype "bidirectional"))
      (node (ref "BAR3") (pin "11") (pinfunction "A6_11") (pintype "bidirectional"))
      (node (ref "IC1") (pin "15") (pinfunction "SEGF_15") (pintype "output"))
    )
    (net (code "59") (name "/SEGF2") (class "Default")
      (node (ref "BAR1") (pin "11") (pinfunction "A6_11") (pintype "bidirectional"))
      (node (ref "IC2") (pin "15") (pinfunction "SEGF_15") (pintype "output"))
      (node (ref "SEV1") (pin "2") (pinfunction "2F_2") (pintype "bidirectional"))
      (node (ref "SEV2") (pin "2") (pinfunction "2F_2") (pintype "bidirectional"))
      (node (ref "SEV3") (pin "2") (pinfunction "2F_2") (pintype "bidirectional"))
      (node (ref "SEV4") (pin "2") (pinfunction "2F_2") (pintype "bidirectional"))
    )
    (net (code "60") (name "/SEGF3") (class "Default")
      (node (ref "IC3") (pin "15") (pinfunction "SEGF_15") (pintype "output"))
      (node (ref "SEV10") (pin "2") (pinfunction "2F_2") (pintype "bidirectional"))
      (node (ref "SEV5") (pin "2") (pinfunction "2F_2") (pintype "bidirectional"))
      (node (ref "SEV6") (pin "2") (pinfunction "2F_2") (pintype "bidirectional"))
      (node (ref "SEV7") (pin "2") (pinfunction "2F_2") (pintype "bidirectional"))
      (node (ref "SEV8") (pin "2") (pinfunction "2F_2") (pintype "bidirectional"))
      (node (ref "SEV9") (pin "2") (pinfunction "2F_2") (pintype "bidirectional"))
    )
    (net (code "61") (name "/SEGG1") (class "Default")
      (node (ref "BAR2") (pin "5") (pinfunction "A7_5") (pintype "bidirectional"))
      (node (ref "BAR3") (pin "5") (pinfunction "A7_5") (pintype "bidirectional"))
      (node (ref "IC1") (pin "17") (pinfunction "SEGG_17") (pintype "output"))
    )
    (net (code "62") (name "/SEGG2") (class "Default")
      (node (ref "BAR1") (pin "5") (pinfunction "A7_5") (pintype "bidirectional"))
      (node (ref "IC2") (pin "17") (pinfunction "SEGG_17") (pintype "output"))
      (node (ref "SEV1") (pin "3") (pinfunction "3G_3") (pintype "bidirectional"))
      (node (ref "SEV2") (pin "3") (pinfunction "3G_3") (pintype "bidirectional"))
      (node (ref "SEV3") (pin "3") (pinfunction "3G_3") (pintype "bidirectional"))
      (node (ref "SEV4") (pin "3") (pinfunction "3G_3") (pintype "bidirectional"))
    )
    (net (code "63") (name "/SEGG3") (class "Default")
      (node (ref "IC3") (pin "17") (pinfunction "SEGG_17") (pintype "output"))
      (node (ref "SEV10") (pin "3") (pinfunction "3G_3") (pintype "bidirectional"))
      (node (ref "SEV5") (pin "3") (pinfunction "3G_3") (pintype "bidirectional"))
      (node (ref "SEV6") (pin "3") (pinfunction "3G_3") (pintype "bidirectional"))
      (node (ref "SEV7") (pin "3") (pinfunction "3G_3") (pintype "bidirectional"))
      (node (ref "SEV8") (pin "3") (pinfunction "3G_3") (pintype "bidirectional"))
      (node (ref "SEV9") (pin "3") (pinfunction "3G_3") (pintype "bidirectional"))
    )
    (net (code "64") (name "/SOL") (class "Default")
      (node (ref "CONV") (pin "12") (pinfunction "LV4_12") (pintype "bidirectional"))
      (node (ref "FEATHERM0") (pin "5") (pinfunction "GPIOA0_5") (pintype "bidirectional"))
    )
    (net (code "65") (name "/STA") (class "Default")
      (node (ref "FEATHERM0") (pin "17") (pinfunction "GPIOSDA_17") (pintype "bidirectional"))
      (node (ref "J1") (pin "3") (pinfunction "3_3") (pintype "passive"))
      (node (ref "J2") (pin "3") (pinfunction "3_3") (pintype "passive"))
      (node (ref "R10") (pin "P$2") (pinfunction "2_P$2") (pintype "passive"))
    )
    (net (code "66") (name "/VBAT") (class "Default")
      (node (ref "FEATHERM0") (pin "28") (pinfunction "VBAT_28") (pintype "power_in"))
    )
    (net (code "67") (name "3.3V") (class "Default")
      (node (ref "BTN") (pin "P$1") (pinfunction "P$1_P$1") (pintype "bidirectional"))
      (node (ref "BTN1") (pin "P$1") (pinfunction "P$1_P$1") (pintype "bidirectional"))
      (node (ref "CONV") (pin "9") (pinfunction "LVIN_9") (pintype "bidirectional"))
      (node (ref "FEATHERM0") (pin "2") (pinfunction "3V_2") (pintype "power_in"))
      (node (ref "J1") (pin "4") (pinfunction "4_4") (pintype "passive"))
      (node (ref "J2") (pin "4") (pinfunction "4_4") (pintype "passive"))
      (node (ref "R4") (pin "P$2") (pinfunction "2_P$2") (pintype "passive"))
      (node (ref "R5") (pin "P$2") (pinfunction "2_P$2") (pintype "passive"))
      (node (ref "R6") (pin "P$2") (pinfunction "2_P$2") (pintype "passive"))
      (node (ref "SW1") (pin "C1") (pinfunction "C1_C1") (pintype "bidirectional"))
      (node (ref "SW2") (pin "C1") (pinfunction "C1_C1") (pintype "bidirectional"))
    )
    (net (code "68") (name "5V") (class "Default")
      (node (ref "C1") (pin "1") (pinfunction "+_1") (pintype "passive"))
      (node (ref "C2") (pin "1") (pinfunction "1_1") (pintype "passive"))
      (node (ref "C3") (pin "1") (pinfunction "+_1") (pintype "passive"))
      (node (ref "C4") (pin "1") (pinfunction "1_1") (pintype "passive"))
      (node (ref "C5") (pin "1") (pinfunction "+_1") (pintype "passive"))
      (node (ref "C6") (pin "1") (pinfunction "1_1") (pintype "passive"))
      (node (ref "CONV") (pin "3") (pinfunction "HVIN_3") (pintype "bidirectional"))
      (node (ref "FEATHERM0") (pin "26") (pinfunction "USB_26") (pintype "power_in"))
      (node (ref "IC1") (pin "19") (pinfunction "VCC_19") (pintype "power_in"))
      (node (ref "IC2") (pin "19") (pinfunction "VCC_19") (pintype "power_in"))
      (node (ref "IC3") (pin "19") (pinfunction "VCC_19") (pintype "power_in"))
      (node (ref "R1") (pin "P$1") (pinfunction "1_P$1") (pintype "passive"))
      (node (ref "R2") (pin "P$1") (pinfunction "1_P$1") (pintype "passive"))
      (node (ref "R3") (pin "P$1") (pinfunction "1_P$1") (pintype "passive"))
      (node (ref "VREG") (pin "OUT") (pinfunction "OUT_OUT") (pintype "passive"))
    )
    (net (code "69") (name "12V") (class "Default")
      (node (ref "12VIN") (pin "P$2") (pinfunction "P$2_P$2") (pintype "bidirectional"))
      (node (ref "D1") (pin "CAT") (pinfunction "C_CAT") (pintype "passive"))
      (node (ref "SOUT") (pin "P$2") (pinfunction "P$2_P$2") (pintype "bidirectional"))
      (node (ref "VREG") (pin "IN") (pinfunction "IN_IN") (pintype "input"))
    )
    (net (code "70") (name "GND") (class "Default")
      (node (ref "12VIN") (pin "P$1") (pinfunction "P$1_P$1") (pintype "bidirectional"))
      (node (ref "C1") (pin "2") (pinfunction "-_2") (pintype "passive"))
      (node (ref "C2") (pin "2") (pinfunction "2_2") (pintype "passive"))
      (node (ref "C3") (pin "2") (pinfunction "-_2") (pintype "passive"))
      (node (ref "C4") (pin "2") (pinfunction "2_2") (pintype "passive"))
      (node (ref "C5") (pin "2") (pinfunction "-_2") (pintype "passive"))
      (node (ref "C6") (pin "2") (pinfunction "2_2") (pintype "passive"))
      (node (ref "CONV") (pin "GND") (pinfunction "HGND_GND") (pintype "bidirectional"))
      (node (ref "CONV") (pin "GND2") (pinfunction "LGDN_GND2") (pintype "bidirectional"))
      (node (ref "FEATHERM0") (pin "4") (pinfunction "GND_4") (pintype "power_in"))
      (node (ref "IC1") (pin "4") (pinfunction "GND_4") (pintype "power_in"))
      (node (ref "IC1") (pin "9") (pinfunction "GND_9") (pintype "power_in"))
      (node (ref "IC2") (pin "4") (pinfunction "GND_4") (pintype "power_in"))
      (node (ref "IC2") (pin "9") (pinfunction "GND_9") (pintype "power_in"))
      (node (ref "IC3") (pin "4") (pinfunction "GND_4") (pintype "power_in"))
      (node (ref "IC3") (pin "9") (pinfunction "GND_9") (pintype "power_in"))
      (node (ref "J1") (pin "1") (pinfunction "1_1") (pintype "passive"))
      (node (ref "J2") (pin "1") (pinfunction "1_1") (pintype "passive"))
      (node (ref "MOSFET") (pin "OUT") (pinfunction "S_OUT") (pintype "bidirectional"))
      (node (ref "R10") (pin "P$1") (pinfunction "1_P$1") (pintype "passive"))
      (node (ref "R11") (pin "P$1") (pinfunction "1_P$1") (pintype "passive"))
      (node (ref "R4") (pin "P$1") (pinfunction "1_P$1") (pintype "passive"))
      (node (ref "R5") (pin "P$1") (pinfunction "1_P$1") (pintype "passive"))
      (node (ref "R6") (pin "P$1") (pinfunction "1_P$1") (pintype "passive"))
      (node (ref "R7") (pin "P$1") (pinfunction "1_P$1") (pintype "passive"))
      (node (ref "R8") (pin "P$1") (pinfunction "1_P$1") (pintype "passive"))
      (node (ref "R9") (pin "P$1") (pinfunction "1_P$1") (pintype "passive"))
      (node (ref "VREG") (pin "GND") (pinfunction "GND_GND") (pintype "input"))
    )
    (net (code "71") (name "Net-(CONV-HV4)") (class "Default")
      (node (ref "CONV") (pin "6") (pinfunction "HV4_6") (pintype "bidirectional"))
      (node (ref "MOSFET") (pin "IN") (pinfunction "G_IN") (pintype "bidirectional"))
    )
    (net (code "72") (name "Net-(D1-A)") (class "Default")
      (node (ref "D1") (pin "ANOD") (pinfunction "A_ANOD") (pintype "passive"))
      (node (ref "MOSFET") (pin "GND") (pinfunction "D_GND") (pintype "bidirectional"))
      (node (ref "SOUT") (pin "P$1") (pinfunction "P$1_P$1") (pintype "bidirectional"))
    )
    (net (code "73") (name "Net-(IC1-ISET)") (class "Default")
      (node (ref "IC1") (pin "18") (pinfunction "ISET_18") (pintype "input"))
      (node (ref "R1") (pin "P$2") (pinfunction "2_P$2") (pintype "passive"))
    )
    (net (code "74") (name "Net-(IC2-ISET)") (class "Default")
      (node (ref "IC2") (pin "18") (pinfunction "ISET_18") (pintype "input"))
      (node (ref "R2") (pin "P$2") (pinfunction "2_P$2") (pintype "passive"))
    )
    (net (code "75") (name "Net-(IC3-ISET)") (class "Default")
      (node (ref "IC3") (pin "18") (pinfunction "ISET_18") (pintype "input"))
      (node (ref "R3") (pin "P$2") (pinfunction "2_P$2") (pintype "passive"))
    )
    (net (code "76") (name "unconnected-(FEATHERM0-AREF-Pad3)") (class "Default")
      (node (ref "FEATHERM0") (pin "3") (pinfunction "AREF_3") (pintype "passive"))
    )
    (net (code "77") (name "unconnected-(FEATHERM0-EN-Pad27)") (class "Default")
      (node (ref "FEATHERM0") (pin "27") (pinfunction "EN_27") (pintype "passive"))
    )
    (net (code "78") (name "unconnected-(FEATHERM0-GPIO13-Pad25)") (class "Default")
      (node (ref "FEATHERM0") (pin "25") (pinfunction "GPIO13_25") (pintype "bidirectional"))
    )
    (net (code "79") (name "unconnected-(FEATHERM0-GPIOA1-Pad6)") (class "Default")
      (node (ref "FEATHERM0") (pin "6") (pinfunction "GPIOA1_6") (pintype "bidirectional"))
    )
    (net (code "80") (name "unconnected-(FEATHERM0-GPIOA2-Pad7)") (class "Default")
      (node (ref "FEATHERM0") (pin "7") (pinfunction "GPIOA2_7") (pintype "bidirectional"))
    )
    (net (code "81") (name "unconnected-(FEATHERM0-GPIOA3-Pad8)") (class "Default")
      (node (ref "FEATHERM0") (pin "8") (pinfunction "GPIOA3_8") (pintype "bidirectional"))
    )
    (net (code "82") (name "unconnected-(FEATHERM0-GPIOA4-Pad9)") (class "Default")
      (node (ref "FEATHERM0") (pin "9") (pinfunction "GPIOA4_9") (pintype "bidirectional"))
    )
    (net (code "83") (name "unconnected-(FEATHERM0-GPIOA5-Pad10)") (class "Default")
      (node (ref "FEATHERM0") (pin "10") (pinfunction "GPIOA5_10") (pintype "bidirectional"))
    )
    (net (code "84") (name "unconnected-(FEATHERM0-GPIOMISO-Pad13)") (class "Default")
      (node (ref "FEATHERM0") (pin "13") (pinfunction "GPIOMISO_13") (pintype "bidirectional"))
    )
    (net (code "85") (name "unconnected-(FEATHERM0-GPIOMOSI-Pad12)") (class "Default")
      (node (ref "FEATHERM0") (pin "12") (pinfunction "GPIOMOSI_12") (pintype "bidirectional"))
    )
    (net (code "86") (name "unconnected-(FEATHERM0-GPIORX-Pad14)") (class "Default")
      (node (ref "FEATHERM0") (pin "14") (pinfunction "GPIORX_14") (pintype "bidirectional"))
    )
    (net (code "87") (name "unconnected-(FEATHERM0-GPIOSCK-Pad11)") (class "Default")
      (node (ref "FEATHERM0") (pin "11") (pinfunction "GPIOSCK_11") (pintype "bidirectional"))
    )
    (net (code "88") (name "unconnected-(FEATHERM0-GPIOTX-Pad15)") (class "Default")
      (node (ref "FEATHERM0") (pin "15") (pinfunction "GPIOTX_15") (pintype "bidirectional"))
    )
    (net (code "89") (name "unconnected-(FEATHERM0-NC-Pad16)") (class "Default")
      (node (ref "FEATHERM0") (pin "16") (pinfunction "NC_16") (pintype "passive"))
    )
    (net (code "90") (name "unconnected-(IC1-DIG6-Pad5)") (class "Default")
      (node (ref "IC1") (pin "5") (pinfunction "DIG6_5") (pintype "output"))
    )
    (net (code "91") (name "unconnected-(IC1-DIG7-Pad8)") (class "Default")
      (node (ref "IC1") (pin "8") (pinfunction "DIG7_8") (pintype "output"))
    )
    (net (code "92") (name "unconnected-(IC2-DIG7-Pad8)") (class "Default")
      (node (ref "IC2") (pin "8") (pinfunction "DIG7_8") (pintype "output"))
    )
    (net (code "93") (name "unconnected-(IC3-DIG6-Pad5)") (class "Default")
      (node (ref "IC3") (pin "5") (pinfunction "DIG6_5") (pintype "output"))
    )
    (net (code "94") (name "unconnected-(IC3-DIG7-Pad8)") (class "Default")
      (node (ref "IC3") (pin "8") (pinfunction "DIG7_8") (pintype "output"))
    )
    (net (code "95") (name "unconnected-(IC3-DOUT-Pad24)") (class "Default")
      (node (ref "IC3") (pin "24") (pinfunction "DOUT_24") (pintype "output"))
    )
    (net (code "96") (name "unconnected-(IC3-SEGDP-Pad22)") (class "Default")
      (node (ref "IC3") (pin "22") (pinfunction "SEGDP_22") (pintype "output"))
    )
    (net (code "97") (name "unconnected-(SW1-Pad4)") (class "Default")
      (node (ref "SW1") (pin "4") (pinfunction "4_4") (pintype "bidirectional"))
    )
    (net (code "98") (name "unconnected-(SW1-Pad5)") (class "Default")
      (node (ref "SW1") (pin "5") (pinfunction "5_5") (pintype "bidirectional"))
    )
    (net (code "99") (name "unconnected-(SW1-Pad6)") (class "Default")
      (node (ref "SW1") (pin "6") (pinfunction "6_6") (pintype "bidirectional"))
    )
    (net (code "100") (name "unconnected-(SW1-PadC2)") (class "Default")
      (node (ref "SW1") (pin "C2") (pinfunction "C2_C2") (pintype "bidirectional"))
    )
    (net (code "101") (name "unconnected-(SW2-Pad4)") (class "Default")
      (node (ref "SW2") (pin "4") (pinfunction "4_4") (pintype "bidirectional"))
    )
    (net (code "102") (name "unconnected-(SW2-Pad5)") (class "Default")
      (node (ref "SW2") (pin "5") (pinfunction "5_5") (pintype "bidirectional"))
    )
    (net (code "103") (name "unconnected-(SW2-Pad6)") (class "Default")
      (node (ref "SW2") (pin "6") (pinfunction "6_6") (pintype "bidirectional"))
    )
    (net (code "104") (name "unconnected-(SW2-PadC2)") (class "Default")
      (node (ref "SW2") (pin "C2") (pinfunction "C2_C2") (pintype "bidirectional"))
    )
  )
)
